# MCU.net
KiCad netlist of a schematic drawn in Altium Designer
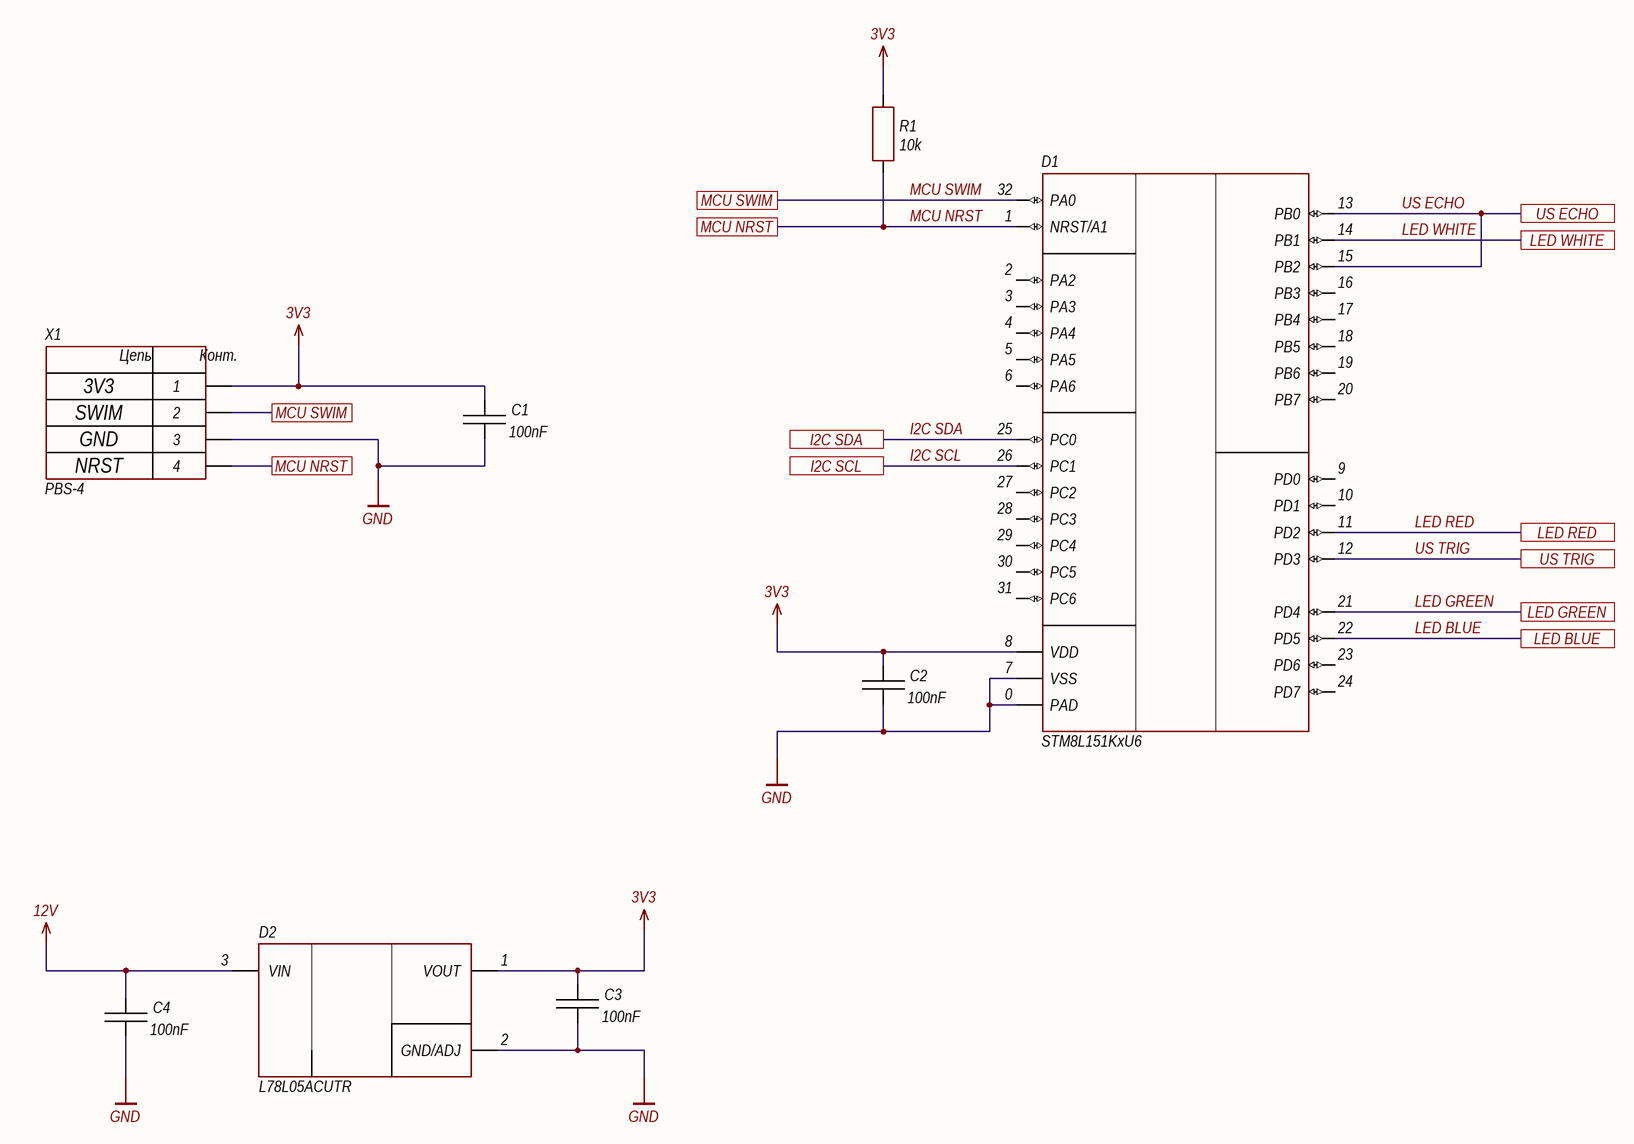
[diagram p0: MCU.SchDoc]

(export (version "E")
  (design (tool "Eeschema 10.0.6"))
  (components
    (comp (ref "C1") (value "100nF") (footprint "CH0603C") (libsource (lib "Discrete") (part "Capacitor")))
    (comp (ref "C2") (value "100nF") (footprint "CH0603C") (libsource (lib "Discrete") (part "Capacitor")))
    (comp (ref "C3") (value "100nF") (footprint "CH0603C") (libsource (lib "Discrete") (part "Capacitor")))
    (comp (ref "C4") (value "100nF") (footprint "CH0603C") (libsource (lib "Discrete") (part "Capacitor")))
    (comp (ref "D1")
      (value "STM8L151KxU6")
      (footprint "32-UFQFPN")
      (description "STM8")
      (fields (field (name "MANUFACTURER") "ST Microelectronics"))
      (libsource (lib "Digital") (part "STM8L151KxU6"))
    )
    (comp (ref "D2")
      (value "L78L05ACUTR")
      (footprint "SOT89_123")
      (description "Step-down")
      (fields (field (name "MANUFACTURER") "ST Microelectronics"))
      (libsource (lib "Power Supplies") (part "L78LxxACUTR"))
    )
    (comp (ref "R1") (value "10k") (footprint "CH0603R") (libsource (lib "Discrete") (part "Resistor")))
    (comp (ref "X1")
      (value "PBS-4")
      (footprint "CON: PBS-4")
      (libsource (lib "Connectors") (part "4-Connector"))
    )
  )
  (nets
    (net (code "1") (name "/I2C SCL") (class "Default")
      (node (ref "D1") (pin "26") (pinfunction "PC1_26") (pintype "bidirectional"))
    )
    (net (code "2") (name "/I2C SDA") (class "Default")
      (node (ref "D1") (pin "25") (pinfunction "PC0_25") (pintype "bidirectional"))
    )
    (net (code "3") (name "/LED BLUE") (class "Default")
      (node (ref "D1") (pin "22") (pinfunction "PD5_22") (pintype "bidirectional"))
    )
    (net (code "4") (name "/LED GREEN") (class "Default")
      (node (ref "D1") (pin "21") (pinfunction "PD4_21") (pintype "bidirectional"))
    )
    (net (code "5") (name "/LED RED") (class "Default")
      (node (ref "D1") (pin "11") (pinfunction "PD2_11") (pintype "bidirectional"))
    )
    (net (code "6") (name "/LED WHITE") (class "Default")
      (node (ref "D1") (pin "14") (pinfunction "PB1_14") (pintype "bidirectional"))
    )
    (net (code "7") (name "/MCU NRST") (class "Default")
      (node (ref "D1") (pin "1") (pinfunction "NRST/A1_1") (pintype "bidirectional"))
      (node (ref "R1") (pin "1") (pinfunction "1_1") (pintype "passive"))
      (node (ref "X1") (pin "4") (pinfunction "4_4") (pintype "power_in"))
    )
    (net (code "8") (name "/MCU SWIM") (class "Default")
      (node (ref "D1") (pin "32") (pinfunction "PA0_32") (pintype "bidirectional"))
      (node (ref "X1") (pin "2") (pinfunction "2_2") (pintype "passive"))
    )
    (net (code "9") (name "/US ECHO") (class "Default")
      (node (ref "D1") (pin "13") (pinfunction "PB0_13") (pintype "bidirectional"))
      (node (ref "D1") (pin "15") (pinfunction "PB2_15") (pintype "bidirectional"))
    )
    (net (code "10") (name "/US TRIG") (class "Default")
      (node (ref "D1") (pin "12") (pinfunction "PD3_12") (pintype "bidirectional"))
    )
    (net (code "11") (name "3V3") (class "Default")
      (node (ref "C1") (pin "2") (pinfunction "2_2") (pintype "power_in"))
      (node (ref "C2") (pin "2") (pinfunction "2_2") (pintype "power_in"))
      (node (ref "C3") (pin "2") (pinfunction "2_2") (pintype "power_in"))
      (node (ref "D1") (pin "8") (pinfunction "VDD_8") (pintype "power_in"))
      (node (ref "D2") (pin "1") (pinfunction "VOUT_1") (pintype "power_in"))
      (node (ref "R1") (pin "2") (pinfunction "2_2") (pintype "passive"))
      (node (ref "X1") (pin "1") (pinfunction "1_1") (pintype "passive"))
    )
    (net (code "12") (name "12V") (class "Default")
      (node (ref "C4") (pin "2") (pinfunction "2_2") (pintype "power_in"))
      (node (ref "D2") (pin "3") (pinfunction "VIN_3") (pintype "power_in"))
    )
    (net (code "13") (name "GND") (class "Default")
      (node (ref "C1") (pin "1") (pinfunction "1_1") (pintype "power_in"))
      (node (ref "C2") (pin "1") (pinfunction "1_1") (pintype "power_in"))
      (node (ref "C3") (pin "1") (pinfunction "1_1") (pintype "power_in"))
      (node (ref "C4") (pin "1") (pinfunction "1_1") (pintype "power_in"))
      (node (ref "D1") (pin "0") (pinfunction "PAD_0") (pintype "power_in"))
      (node (ref "D1") (pin "7") (pinfunction "VSS_7") (pintype "power_in"))
      (node (ref "D2") (pin "2") (pinfunction "GND/ADJ_2") (pintype "power_in"))
      (node (ref "X1") (pin "3") (pinfunction "3_3") (pintype "power_in"))
    )
    (net (code "14") (name "unconnected-(D1-PA2-Pad2)") (class "Default")
      (node (ref "D1") (pin "2") (pinfunction "PA2_2") (pintype "bidirectional"))
    )
    (net (code "15") (name "unconnected-(D1-PA3-Pad3)") (class "Default")
      (node (ref "D1") (pin "3") (pinfunction "PA3_3") (pintype "bidirectional"))
    )
    (net (code "16") (name "unconnected-(D1-PA4-Pad4)") (class "Default")
      (node (ref "D1") (pin "4") (pinfunction "PA4_4") (pintype "bidirectional"))
    )
    (net (code "17") (name "unconnected-(D1-PA5-Pad5)") (class "Default")
      (node (ref "D1") (pin "5") (pinfunction "PA5_5") (pintype "bidirectional"))
    )
    (net (code "18") (name "unconnected-(D1-PA6-Pad6)") (class "Default")
      (node (ref "D1") (pin "6") (pinfunction "PA6_6") (pintype "bidirectional"))
    )
    (net (code "19") (name "unconnected-(D1-PB3-Pad16)") (class "Default")
      (node (ref "D1") (pin "16") (pinfunction "PB3_16") (pintype "bidirectional"))
    )
    (net (code "20") (name "unconnected-(D1-PB4-Pad17)") (class "Default")
      (node (ref "D1") (pin "17") (pinfunction "PB4_17") (pintype "bidirectional"))
    )
    (net (code "21") (name "unconnected-(D1-PB5-Pad18)") (class "Default")
      (node (ref "D1") (pin "18") (pinfunction "PB5_18") (pintype "bidirectional"))
    )
    (net (code "22") (name "unconnected-(D1-PB6-Pad19)") (class "Default")
      (node (ref "D1") (pin "19") (pinfunction "PB6_19") (pintype "bidirectional"))
    )
    (net (code "23") (name "unconnected-(D1-PB7-Pad20)") (class "Default")
      (node (ref "D1") (pin "20") (pinfunction "PB7_20") (pintype "bidirectional"))
    )
    (net (code "24") (name "unconnected-(D1-PC2-Pad27)") (class "Default")
      (node (ref "D1") (pin "27") (pinfunction "PC2_27") (pintype "bidirectional"))
    )
    (net (code "25") (name "unconnected-(D1-PC3-Pad28)") (class "Default")
      (node (ref "D1") (pin "28") (pinfunction "PC3_28") (pintype "bidirectional"))
    )
    (net (code "26") (name "unconnected-(D1-PC4-Pad29)") (class "Default")
      (node (ref "D1") (pin "29") (pinfunction "PC4_29") (pintype "bidirectional"))
    )
    (net (code "27") (name "unconnected-(D1-PC5-Pad30)") (class "Default")
      (node (ref "D1") (pin "30") (pinfunction "PC5_30") (pintype "bidirectional"))
    )
    (net (code "28") (name "unconnected-(D1-PC6-Pad31)") (class "Default")
      (node (ref "D1") (pin "31") (pinfunction "PC6_31") (pintype "bidirectional"))
    )
    (net (code "29") (name "unconnected-(D1-PD0-Pad9)") (class "Default")
      (node (ref "D1") (pin "9") (pinfunction "PD0_9") (pintype "bidirectional"))
    )
    (net (code "30") (name "unconnected-(D1-PD1-Pad10)") (class "Default")
      (node (ref "D1") (pin "10") (pinfunction "PD1_10") (pintype "bidirectional"))
    )
    (net (code "31") (name "unconnected-(D1-PD6-Pad23)") (class "Default")
      (node (ref "D1") (pin "23") (pinfunction "PD6_23") (pintype "bidirectional"))
    )
    (net (code "32") (name "unconnected-(D1-PD7-Pad24)") (class "Default")
      (node (ref "D1") (pin "24") (pinfunction "PD7_24") (pintype "bidirectional"))
    )
  )
)
